# StyroCutter-556-heatsink-5V.net
KiCad netlist of a schematic drawn in EAGLE
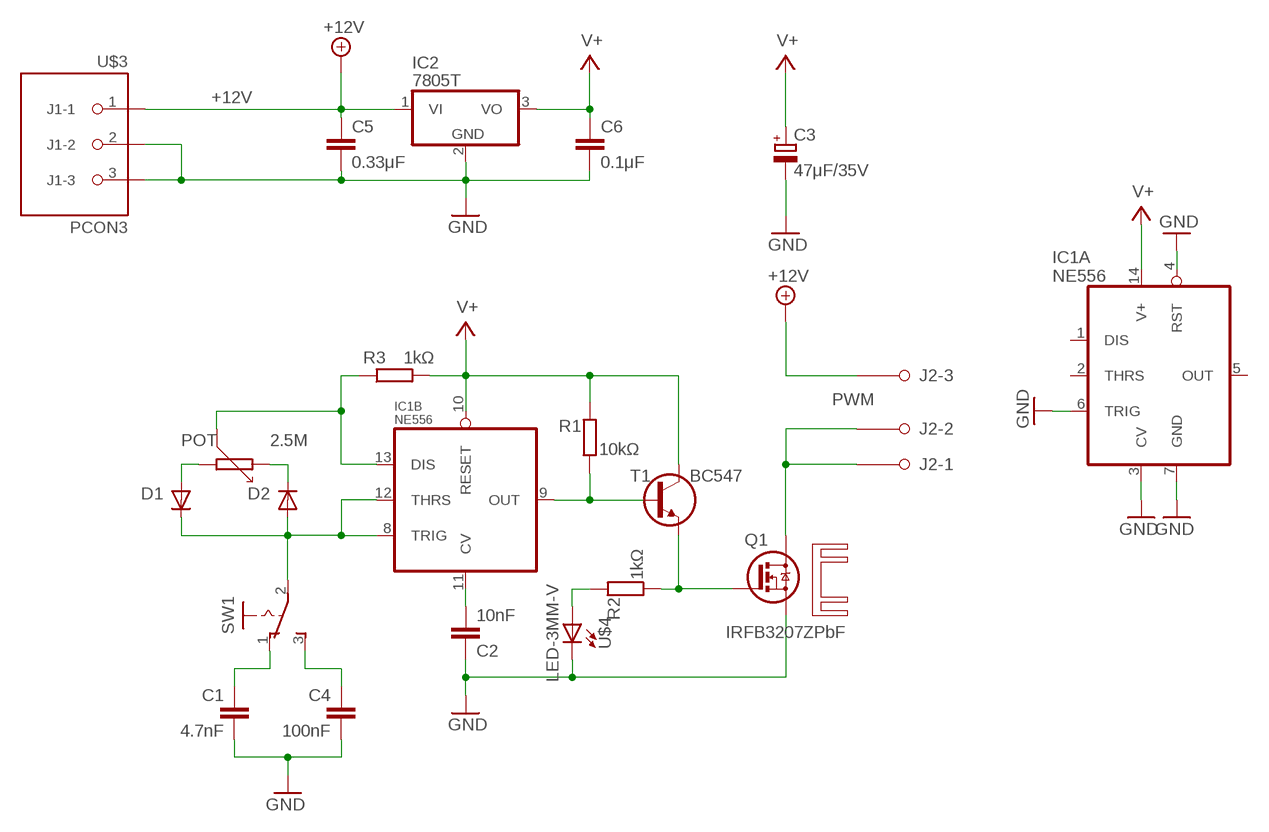
[diagram p0: schematic, sheet 1]

(export (version "E")
  (design (tool "Eeschema 10.0.6"))
  (components
    (comp (ref "C1")
      (value "4.7nF")
      (footprint "eagle-import:C050-020X036")
      (libsource (lib "eagle-import") (part "C050-020X036"))
    )
    (comp (ref "C2")
      (value "10nF")
      (footprint "eagle-import:C050-020X036")
      (libsource (lib "eagle-import") (part "C050-020X036"))
    )
    (comp (ref "C3")
      (value "47μF/35V")
      (footprint "eagle-import:E2,5-5")
      (libsource (lib "eagle-import") (part "CPOL-EUE2.5-5"))
    )
    (comp (ref "C4")
      (value "100nF")
      (footprint "eagle-import:C050-020X036")
      (libsource (lib "eagle-import") (part "C050-020X036"))
    )
    (comp (ref "C5")
      (value "0.33μF")
      (footprint "eagle-import:C050-024X044")
      (libsource (lib "eagle-import") (part "C050-024X044"))
    )
    (comp (ref "C6")
      (value "0.1μF")
      (footprint "eagle-import:C050-024X044")
      (libsource (lib "eagle-import") (part "C050-024X044"))
    )
    (comp (ref "D1")
      (value "1N4148")
      (footprint "eagle-import:DO34-5")
      (libsource (lib "eagle-import") (part "1N414834-5"))
    )
    (comp (ref "D2")
      (value "1N4148")
      (footprint "eagle-import:DO34-5")
      (libsource (lib "eagle-import") (part "1N414834-5"))
    )
    (comp (ref "IC1")
      (value "NE556")
      (footprint "eagle-import:DIL14")
      (libsource (lib "eagle-import") (part "556-ALT-DIL14"))
    )
    (comp (ref "IC2")
      (value "7805T")
      (footprint "eagle-import:TO220H")
      (libsource (lib "eagle-import") (part "78T05"))
    )
    (comp (ref "J2")
      (value "PCON3_MIGROS")
      (footprint "eagle-import:CON-MIGROS-3PIN")
      (libsource (lib "eagle-import") (part "PCON3_MIGROS"))
    )
    (comp (ref "POT")
      (value "2.5M")
      (footprint "eagle-import:PC16S")
      (libsource (lib "eagle-import") (part "PIHER-PT16S"))
    )
    (comp (ref "Q1")
      (value "IRFB3207ZPbF")
      (footprint "eagle-import:TO220BV")
      (libsource (lib "eagle-import") (part "PMOSFET_NTO220BV"))
    )
    (comp (ref "R1")
      (value "10kΩ")
      (footprint "eagle-import:0204_12")
      (libsource (lib "eagle-import") (part "R0204/12"))
    )
    (comp (ref "R2")
      (value "1kΩ")
      (footprint "eagle-import:0204_10")
      (libsource (lib "eagle-import") (part "R0204/10"))
    )
    (comp (ref "R3")
      (value "1kΩ")
      (footprint "eagle-import:0202_2V")
      (libsource (lib "eagle-import") (part "R0202/2V"))
    )
    (comp (ref "SW1")
      (value "SL-SW-1P-2T")
      (footprint "eagle-import:SLSW-1P2T")
      (libsource (lib "eagle-import") (part "SL-SW-1P-2T"))
    )
    (comp (ref "T1")
      (value "BC547")
      (footprint "eagle-import:TO92-CBE")
      (libsource (lib "eagle-import") (part "BC547CBE"))
    )
    (comp (ref "U$2")
      (value "AQ-SO")
      (footprint "eagle-import:AQ_HS_3A_SO")
      (libsource (lib "eagle-import") (part "AQ-SO"))
    )
    (comp (ref "U$3")
      (value "PCON3")
      (footprint "eagle-import:CON-MIGROS-3PIN")
      (libsource (lib "eagle-import") (part "PCON3"))
    )
    (comp (ref "U$4")
      (value "LED-3MM-V")
      (footprint "eagle-import:LED-3MM-V")
      (libsource (lib "eagle-import") (part "LED-3MM-V"))
    )
  )
  (nets
    (net (code "1") (name "+12V") (class "Default")
      (node (ref "C5") (pin "1") (pinfunction "1_1") (pintype "passive"))
      (node (ref "IC2") (pin "1") (pinfunction "VI_1") (pintype "input"))
      (node (ref "J2") (pin "3") (pinfunction "1_3") (pintype "bidirectional"))
      (node (ref "U$3") (pin "1") (pinfunction "J1-1_1") (pintype "passive"))
    )
    (net (code "2") (name "/PWM") (class "Default")
      (node (ref "J2") (pin "1") (pinfunction "1_1") (pintype "bidirectional"))
      (node (ref "J2") (pin "2") (pinfunction "1_2") (pintype "bidirectional"))
      (node (ref "Q1") (pin "D") (pinfunction "D_D") (pintype "passive"))
    )
    (net (code "3") (name "GND") (class "Default")
      (node (ref "C1") (pin "2") (pinfunction "2_2") (pintype "passive"))
      (node (ref "C2") (pin "1") (pinfunction "1_1") (pintype "passive"))
      (node (ref "C3") (pin "-") (pinfunction "-_-") (pintype "passive"))
      (node (ref "C4") (pin "2") (pinfunction "2_2") (pintype "passive"))
      (node (ref "C5") (pin "2") (pinfunction "2_2") (pintype "passive"))
      (node (ref "C6") (pin "2") (pinfunction "2_2") (pintype "passive"))
      (node (ref "IC1") (pin "3") (pinfunction "CV_3") (pintype "input"))
      (node (ref "IC1") (pin "4") (pinfunction "RST_4") (pintype "input"))
      (node (ref "IC1") (pin "6") (pinfunction "TRIG_6") (pintype "input"))
      (node (ref "IC1") (pin "7") (pinfunction "GND_7") (pintype "power_in"))
      (node (ref "IC2") (pin "2") (pinfunction "GND_2") (pintype "passive"))
      (node (ref "Q1") (pin "S") (pinfunction "S_S") (pintype "passive"))
      (node (ref "U$3") (pin "2") (pinfunction "J1-2_2") (pintype "passive"))
      (node (ref "U$3") (pin "3") (pinfunction "J1-3_3") (pintype "passive"))
      (node (ref "U$4") (pin "C") (pinfunction "C_C") (pintype "passive"))
    )
    (net (code "4") (name "Net-(D1-PadA)") (class "Default")
      (node (ref "D1") (pin "A") (pinfunction "A_A") (pintype "passive"))
      (node (ref "POT") (pin "1E") (pinfunction "1E_1E") (pintype "passive"))
    )
    (net (code "5") (name "Net-(D2-PadC)") (class "Default")
      (node (ref "D2") (pin "C") (pinfunction "C_C") (pintype "passive"))
      (node (ref "POT") (pin "1A") (pinfunction "1A_1A") (pintype "passive"))
    )
    (net (code "6") (name "Net-(IC1B-CV)") (class "Default")
      (node (ref "C2") (pin "2") (pinfunction "2_2") (pintype "passive"))
      (node (ref "IC1") (pin "11") (pinfunction "CV_11") (pintype "input"))
    )
    (net (code "7") (name "Net-(IC1B-DIS)") (class "Default")
      (node (ref "IC1") (pin "13") (pinfunction "DIS_13") (pintype "input"))
      (node (ref "POT") (pin "1S") (pinfunction "1S_1S") (pintype "passive"))
      (node (ref "R3") (pin "1") (pinfunction "1_1") (pintype "passive"))
    )
    (net (code "8") (name "Net-(IC1B-OUT)") (class "Default")
      (node (ref "IC1") (pin "9") (pinfunction "OUT_9") (pintype "output"))
      (node (ref "R1") (pin "1") (pinfunction "1_1") (pintype "passive"))
      (node (ref "T1") (pin "B") (pinfunction "B_B") (pintype "passive"))
    )
    (net (code "9") (name "Net-(IC1B-THRS)") (class "Default")
      (node (ref "D1") (pin "C") (pinfunction "C_C") (pintype "passive"))
      (node (ref "D2") (pin "A") (pinfunction "A_A") (pintype "passive"))
      (node (ref "IC1") (pin "12") (pinfunction "THRS_12") (pintype "input"))
      (node (ref "IC1") (pin "8") (pinfunction "TRIG_8") (pintype "input"))
      (node (ref "SW1") (pin "2") (pinfunction "P_2") (pintype "passive"))
    )
    (net (code "10") (name "Net-(Q1-PadG)") (class "Default")
      (node (ref "Q1") (pin "G") (pinfunction "G_G") (pintype "passive"))
      (node (ref "R2") (pin "1") (pinfunction "1_1") (pintype "passive"))
      (node (ref "T1") (pin "E") (pinfunction "E_E") (pintype "passive"))
    )
    (net (code "11") (name "Net-(R2-Pad2)") (class "Default")
      (node (ref "R2") (pin "2") (pinfunction "2_2") (pintype "passive"))
      (node (ref "U$4") (pin "A") (pinfunction "A_A") (pintype "passive"))
    )
    (net (code "12") (name "Net-(SW1-O)") (class "Default")
      (node (ref "C1") (pin "1") (pinfunction "1_1") (pintype "passive"))
      (node (ref "SW1") (pin "1") (pinfunction "O_1") (pintype "passive"))
    )
    (net (code "13") (name "Net-(SW1-S)") (class "Default")
      (node (ref "C4") (pin "1") (pinfunction "1_1") (pintype "passive"))
      (node (ref "SW1") (pin "3") (pinfunction "S_3") (pintype "passive"))
    )
    (net (code "14") (name "V+") (class "Default")
      (node (ref "C3") (pin "+") (pinfunction "+_+") (pintype "passive"))
      (node (ref "C6") (pin "1") (pinfunction "1_1") (pintype "passive"))
      (node (ref "IC1") (pin "10") (pinfunction "RESET_10") (pintype "input"))
      (node (ref "IC1") (pin "14") (pinfunction "V+_14") (pintype "power_in"))
      (node (ref "IC2") (pin "3") (pinfunction "VO_3") (pintype "passive"))
      (node (ref "R1") (pin "2") (pinfunction "2_2") (pintype "passive"))
      (node (ref "R3") (pin "2") (pinfunction "2_2") (pintype "passive"))
      (node (ref "T1") (pin "C") (pinfunction "C_C") (pintype "passive"))
    )
    (net (code "15") (name "unconnected-(IC1A-DIS-Pad1)") (class "Default")
      (node (ref "IC1") (pin "1") (pinfunction "DIS_1") (pintype "input"))
    )
    (net (code "16") (name "unconnected-(IC1A-OUT-Pad5)") (class "Default")
      (node (ref "IC1") (pin "5") (pinfunction "OUT_5") (pintype "output"))
    )
    (net (code "17") (name "unconnected-(IC1A-THRS-Pad2)") (class "Default")
      (node (ref "IC1") (pin "2") (pinfunction "THRS_2") (pintype "input"))
    )
  )
)
